# MB_Relay_Active_LOW.net
KiCad netlist of a schematic drawn in EAGLE
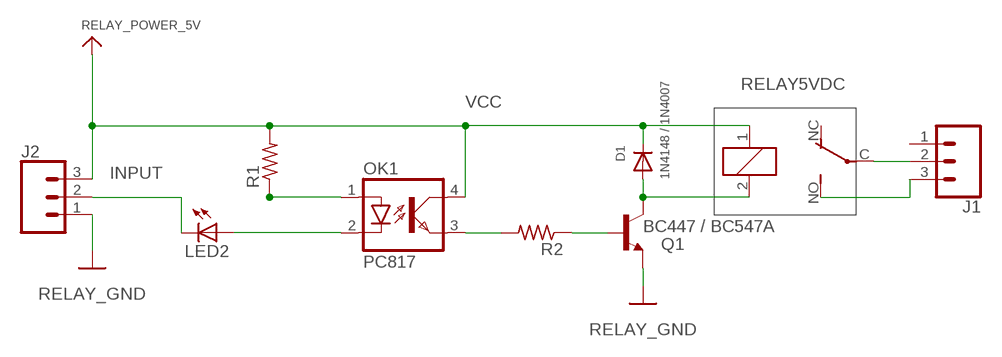
[diagram p0: schematic, sheet 1]

(export (version "E")
  (design (tool "Eeschema 10.0.6"))
  (components
    (comp (ref "D1")
      (value "1N4148 / 1N4007")
      (footprint "eagle-import:DO-1N4148")
      (libsource (lib "eagle-import") (part "DIODEDO-1N4148"))
    )
    (comp (ref "J1")
      (value "CONN_03")
      (footprint "eagle-import:1X03")
      (libsource (lib "eagle-import") (part "CONN_03"))
    )
    (comp (ref "J2")
      (value "CONN_03")
      (footprint "eagle-import:1X03")
      (libsource (lib "eagle-import") (part "CONN_03"))
    )
    (comp (ref "LED2")
      (value "LED3MM")
      (footprint "eagle-import:LED3MM")
      (libsource (lib "eagle-import") (part "LED3MM"))
    )
    (comp (ref "OK1")
      (value "PC817")
      (footprint "eagle-import:DIL04")
      (fields (field (name "MPN") "PC817X4J000F"))
      (libsource (lib "eagle-import") (part "PC817"))
    )
    (comp (ref "Q1")
      (value "BC447 / BC547A")
      (footprint "eagle-import:TO92-EBC")
      (libsource (lib "eagle-import") (part "BC447"))
    )
    (comp (ref "R1")
      (value "R-US_0207/7")
      (footprint "eagle-import:0207_7")
      (libsource (lib "eagle-import") (part "R-US_0207/7"))
    )
    (comp (ref "R2")
      (value "R-US_0207/7")
      (footprint "eagle-import:0207_7")
      (libsource (lib "eagle-import") (part "R-US_0207/7"))
    )
    (comp (ref "RELAY5VDC")
      (value "RELAY 5VDC")
      (footprint "eagle-import:CQ1")
      (libsource (lib "eagle-import") (part "CQ1-12V"))
    )
  )
  (nets
    (net (code "1") (name "/INPUT") (class "Default")
      (node (ref "J2") (pin "2") (pinfunction "2_2") (pintype "passive"))
      (node (ref "LED2") (pin "K") (pinfunction "C_K") (pintype "passive"))
    )
    (net (code "2") (name "Net-(D1-PadA)") (class "Default")
      (node (ref "D1") (pin "A") (pinfunction "A_A") (pintype "passive"))
      (node (ref "Q1") (pin "C") (pinfunction "C_C") (pintype "passive"))
      (node (ref "RELAY5VDC") (pin "2") (pinfunction "2_2") (pintype "passive"))
    )
    (net (code "3") (name "Net-(OK1-A)") (class "Default")
      (node (ref "OK1") (pin "1") (pinfunction "A_1") (pintype "passive"))
      (node (ref "R1") (pin "1") (pinfunction "1_1") (pintype "passive"))
    )
    (net (code "4") (name "Net-(OK1-C)") (class "Default")
      (node (ref "LED2") (pin "A") (pinfunction "A_A") (pintype "passive"))
      (node (ref "OK1") (pin "2") (pinfunction "C_2") (pintype "passive"))
    )
    (net (code "5") (name "Net-(OK1-EMIT)") (class "Default")
      (node (ref "OK1") (pin "3") (pinfunction "EMIT_3") (pintype "passive"))
      (node (ref "R2") (pin "2") (pinfunction "2_2") (pintype "passive"))
    )
    (net (code "6") (name "Net-(Q1-PadB)") (class "Default")
      (node (ref "Q1") (pin "B") (pinfunction "B_B") (pintype "passive"))
      (node (ref "R2") (pin "1") (pinfunction "1_1") (pintype "passive"))
    )
    (net (code "7") (name "Net-(RELAY5VDCB-P)") (class "Default")
      (node (ref "J1") (pin "2") (pinfunction "2_2") (pintype "passive"))
      (node (ref "RELAY5VDC") (pin "C") (pinfunction "P_C") (pintype "passive"))
    )
    (net (code "8") (name "Net-(RELAY5VDCB-S)") (class "Default")
      (node (ref "J1") (pin "3") (pinfunction "3_3") (pintype "passive"))
      (node (ref "RELAY5VDC") (pin "NO") (pinfunction "S_NO") (pintype "passive"))
    )
    (net (code "9") (name "RELAY_GND") (class "Default")
      (node (ref "J2") (pin "1") (pinfunction "1_1") (pintype "passive"))
      (node (ref "Q1") (pin "E") (pinfunction "E_E") (pintype "passive"))
    )
    (net (code "10") (name "RELAY_POWER_5V") (class "Default")
      (node (ref "D1") (pin "C") (pinfunction "C_C") (pintype "passive"))
      (node (ref "J2") (pin "3") (pinfunction "3_3") (pintype "passive"))
      (node (ref "OK1") (pin "4") (pinfunction "COL_4") (pintype "passive"))
      (node (ref "R1") (pin "2") (pinfunction "2_2") (pintype "passive"))
      (node (ref "RELAY5VDC") (pin "1") (pinfunction "1_1") (pintype "passive"))
    )
    (net (code "11") (name "unconnected-(J1-Pad1)") (class "Default")
      (node (ref "J1") (pin "1") (pinfunction "1_1") (pintype "passive"))
    )
    (net (code "12") (name "unconnected-(RELAY5VDCB-O-PadNC)") (class "Default")
      (node (ref "RELAY5VDC") (pin "NC") (pinfunction "O_NC") (pintype "passive"))
    )
  )
)
